# TestServoCircuit.net
KiCad netlist of a schematic drawn in Altium Designer
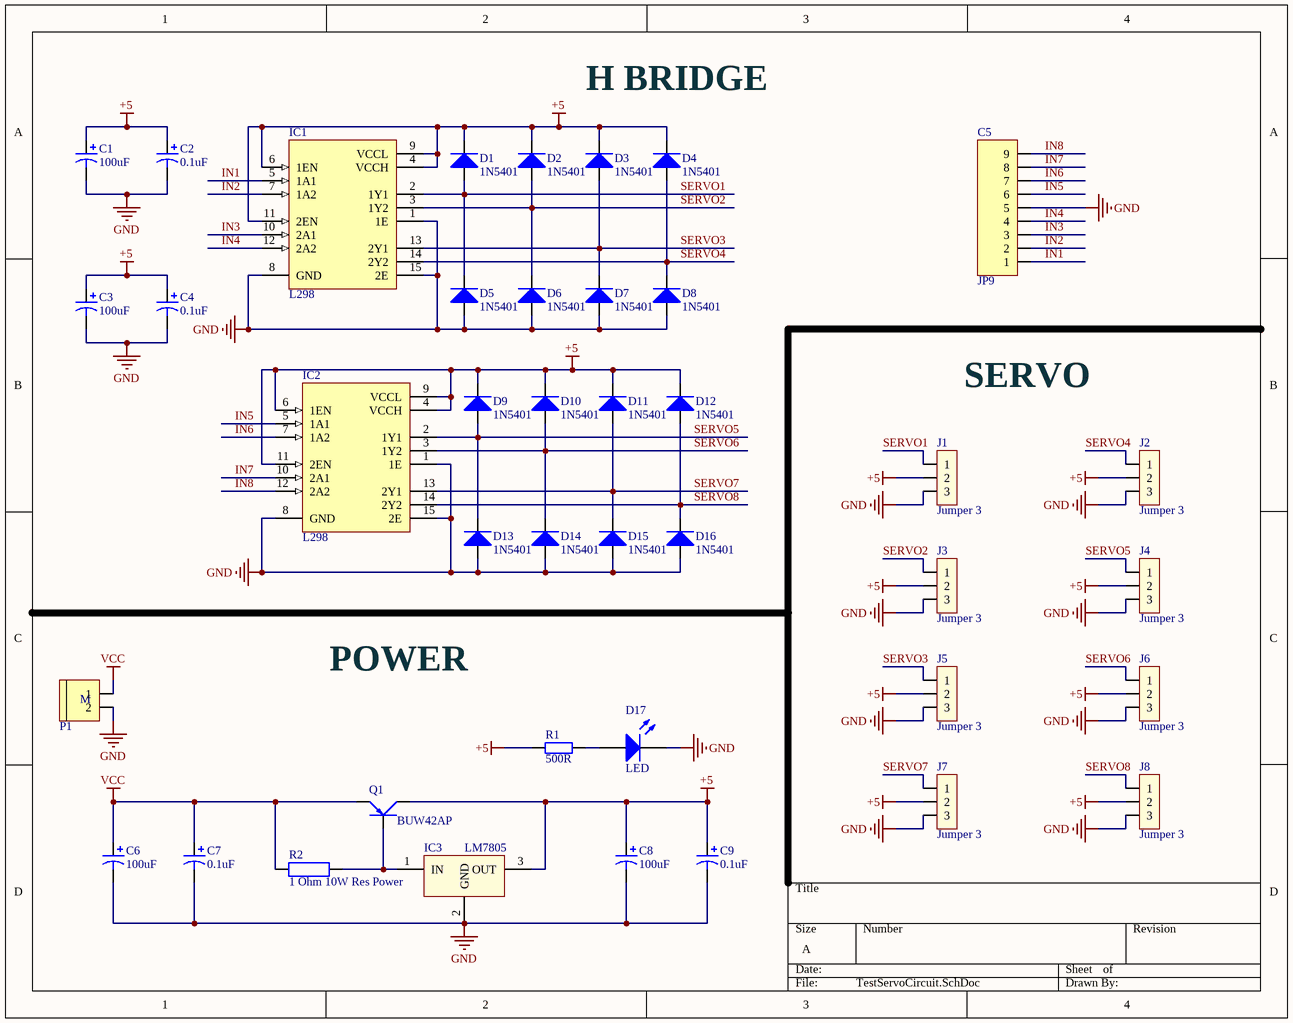
[diagram p0: TestServoCircuit.SchDoc]

(export (version "E")
  (design (tool "Eeschema 10.0.6"))
  (components
    (comp (ref "C1")
      (value "100uF")
      (footprint "MinhTien_PCBLib:CAPPR3-8x12")
      (description "Polarized Capacitor")
      (fields (field (name "Comment") "Cap Polar") (field (name "PUBLISHER") "Altium Limited"))
      (libsource (lib "MinhTien_SCHLib") (part "Cap Polar"))
    )
    (comp (ref "C2")
      (value "0.1uF")
      (footprint "MinhTien_PCBLib:CAPPR2-5x11")
      (description "Polarized Capacitor")
      (fields (field (name "Comment") "Cap Polar") (field (name "PUBLISHER") "Altium Limited"))
      (libsource (lib "MinhTien_SCHLib") (part "Cap Polar"))
    )
    (comp (ref "C3")
      (value "100uF")
      (footprint "MinhTien_PCBLib:CAPPR3-8x12")
      (description "Polarized Capacitor")
      (fields (field (name "Comment") "Cap Polar") (field (name "PUBLISHER") "Altium Limited"))
      (libsource (lib "MinhTien_SCHLib") (part "Cap Polar"))
    )
    (comp (ref "C4")
      (value "0.1uF")
      (footprint "MinhTien_PCBLib:CAPPR2-5x11")
      (description "Polarized Capacitor")
      (fields (field (name "Comment") "Cap Polar") (field (name "PUBLISHER") "Altium Limited"))
      (libsource (lib "MinhTien_SCHLib") (part "Cap Polar"))
    )
    (comp (ref "C5")
      (value "JP9")
      (footprint "JP9-D1T")
      (description "WR-PHD 2.54 mm Angled Socket Header")
      (fields
        (field (name "MANUFACTURER") "Würth Elektronik eiSos GmbH")
        (field (name "PARTNO") "613009143121")
        (field (name "CREATED BY") "Karrer Zheng")
      )
      (libsource (lib "LIBRARY") (part "JP9"))
    )
    (comp (ref "C6")
      (value "100uF")
      (footprint "MinhTien_PCBLib:CAPPR3-8x12")
      (description "Polarized Capacitor")
      (fields (field (name "Comment") "Cap Polar") (field (name "PUBLISHER") "Altium Limited"))
      (libsource (lib "MinhTien_SCHLib") (part "Cap Polar"))
    )
    (comp (ref "C7")
      (value "0.1uF")
      (footprint "MinhTien_PCBLib:CAPPR2-5x11")
      (description "Polarized Capacitor")
      (fields (field (name "Comment") "Cap Polar") (field (name "PUBLISHER") "Altium Limited"))
      (libsource (lib "MinhTien_SCHLib") (part "Cap Polar"))
    )
    (comp (ref "C8")
      (value "100uF")
      (footprint "MinhTien_PCBLib:CAPPR3-8x12")
      (description "Polarized Capacitor")
      (fields (field (name "Comment") "Cap Polar") (field (name "PUBLISHER") "Altium Limited"))
      (libsource (lib "MinhTien_SCHLib") (part "Cap Polar"))
    )
    (comp (ref "C9")
      (value "0.1uF")
      (footprint "MinhTien_PCBLib:CAPPR2-5x11")
      (description "Polarized Capacitor")
      (fields (field (name "Comment") "Cap Polar") (field (name "PUBLISHER") "Altium Limited"))
      (libsource (lib "MinhTien_SCHLib") (part "Cap Polar"))
    )
    (comp (ref "D1")
      (value "1N5401")
      (footprint "MinhTien_PcbLib:DIODE/POW/3A")
      (description "Default Diode")
      (fields (field (name "PUBLISHER") "Altium Limited"))
      (libsource (lib "MinhTien_SCHLib") (part "Diode"))
    )
    (comp (ref "D2")
      (value "1N5401")
      (footprint "MinhTien_PcbLib:DIODE/POW/3A")
      (description "Default Diode")
      (fields (field (name "PUBLISHER") "Altium Limited"))
      (libsource (lib "MinhTien_SCHLib") (part "Diode"))
    )
    (comp (ref "D3")
      (value "1N5401")
      (footprint "MinhTien_PcbLib:DIODE/POW/3A")
      (description "Default Diode")
      (fields (field (name "PUBLISHER") "Altium Limited"))
      (libsource (lib "MinhTien_SCHLib") (part "Diode"))
    )
    (comp (ref "D4")
      (value "1N5401")
      (footprint "MinhTien_PcbLib:DIODE/POW/3A")
      (description "Default Diode")
      (fields (field (name "PUBLISHER") "Altium Limited"))
      (libsource (lib "MinhTien_SCHLib") (part "Diode"))
    )
    (comp (ref "D5")
      (value "1N5401")
      (footprint "MinhTien_PcbLib:DIODE/POW/3A")
      (description "Default Diode")
      (fields (field (name "PUBLISHER") "Altium Limited"))
      (libsource (lib "MinhTien_SCHLib") (part "Diode"))
    )
    (comp (ref "D6")
      (value "1N5401")
      (footprint "MinhTien_PcbLib:DIODE/POW/3A")
      (description "Default Diode")
      (fields (field (name "PUBLISHER") "Altium Limited"))
      (libsource (lib "MinhTien_SCHLib") (part "Diode"))
    )
    (comp (ref "D7")
      (value "1N5401")
      (footprint "MinhTien_PcbLib:DIODE/POW/3A")
      (description "Default Diode")
      (fields (field (name "PUBLISHER") "Altium Limited"))
      (libsource (lib "MinhTien_SCHLib") (part "Diode"))
    )
    (comp (ref "D8")
      (value "1N5401")
      (footprint "MinhTien_PcbLib:DIODE/POW/3A")
      (description "Default Diode")
      (fields (field (name "PUBLISHER") "Altium Limited"))
      (libsource (lib "MinhTien_SCHLib") (part "Diode"))
    )
    (comp (ref "D9")
      (value "1N5401")
      (footprint "MinhTien_PcbLib:DIODE/POW/3A")
      (description "Default Diode")
      (fields (field (name "PUBLISHER") "Altium Limited"))
      (libsource (lib "MinhTien_SCHLib") (part "Diode"))
    )
    (comp (ref "D10")
      (value "1N5401")
      (footprint "MinhTien_PcbLib:DIODE/POW/3A")
      (description "Default Diode")
      (fields (field (name "PUBLISHER") "Altium Limited"))
      (libsource (lib "MinhTien_SCHLib") (part "Diode"))
    )
    (comp (ref "D11")
      (value "1N5401")
      (footprint "MinhTien_PcbLib:DIODE/POW/3A")
      (description "Default Diode")
      (fields (field (name "PUBLISHER") "Altium Limited"))
      (libsource (lib "MinhTien_SCHLib") (part "Diode"))
    )
    (comp (ref "D12")
      (value "1N5401")
      (footprint "MinhTien_PcbLib:DIODE/POW/3A")
      (description "Default Diode")
      (fields (field (name "PUBLISHER") "Altium Limited"))
      (libsource (lib "MinhTien_SCHLib") (part "Diode"))
    )
    (comp (ref "D13")
      (value "1N5401")
      (footprint "MinhTien_PcbLib:DIODE/POW/3A")
      (description "Default Diode")
      (fields (field (name "PUBLISHER") "Altium Limited"))
      (libsource (lib "MinhTien_SCHLib") (part "Diode"))
    )
    (comp (ref "D14")
      (value "1N5401")
      (footprint "MinhTien_PcbLib:DIODE/POW/3A")
      (description "Default Diode")
      (fields (field (name "PUBLISHER") "Altium Limited"))
      (libsource (lib "MinhTien_SCHLib") (part "Diode"))
    )
    (comp (ref "D15")
      (value "1N5401")
      (footprint "MinhTien_PcbLib:DIODE/POW/3A")
      (description "Default Diode")
      (fields (field (name "PUBLISHER") "Altium Limited"))
      (libsource (lib "MinhTien_SCHLib") (part "Diode"))
    )
    (comp (ref "D16")
      (value "1N5401")
      (footprint "MinhTien_PcbLib:DIODE/POW/3A")
      (description "Default Diode")
      (fields (field (name "PUBLISHER") "Altium Limited"))
      (libsource (lib "MinhTien_SCHLib") (part "Diode"))
    )
    (comp (ref "D17")
      (value "LED")
      (footprint "MinhTien_PcbLib:LED_5mm")
      (description "Typical INFRARED GaAs LED")
      (fields (field (name "PUBLISHER") "Altium Limited"))
      (libsource (lib "MinhTien_SCHLib") (part "LED"))
    )
    (comp (ref "IC1")
      (value "L298")
      (footprint "DIP15SL2")
      (description "Dual Full-H Driver")
      (fields (field (name "PUBLISHER") "Altium Limited"))
      (libsource (lib "LIBRARY") (part "L298"))
    )
    (comp (ref "IC2")
      (value "L298")
      (footprint "DIP15SL2")
      (description "Dual Full-H Driver")
      (fields (field (name "PUBLISHER") "Altium Limited"))
      (libsource (lib "LIBRARY") (part "L298"))
    )
    (comp (ref "IC3")
      (value "LM7805")
      (footprint "QTO-220")
      (description "On ap +, from + 5 to + 24VDC")
      (libsource (lib "My Library") (part "LM78xx"))
    )
    (comp (ref "J1") (value "Jumper 3") (footprint "JP3") (libsource (lib "Cty1") (part "JP3")))
    (comp (ref "J2") (value "Jumper 3") (footprint "JP3") (libsource (lib "Cty1") (part "JP3")))
    (comp (ref "J3") (value "Jumper 3") (footprint "JP3") (libsource (lib "Cty1") (part "JP3")))
    (comp (ref "J4") (value "Jumper 3") (footprint "JP3") (libsource (lib "Cty1") (part "JP3")))
    (comp (ref "J5") (value "Jumper 3") (footprint "JP3") (libsource (lib "Cty1") (part "JP3")))
    (comp (ref "J6") (value "Jumper 3") (footprint "JP3") (libsource (lib "Cty1") (part "JP3")))
    (comp (ref "J7") (value "Jumper 3") (footprint "JP3") (libsource (lib "Cty1") (part "JP3")))
    (comp (ref "J8") (value "Jumper 3") (footprint "JP3") (libsource (lib "Cty1") (part "JP3")))
    (comp (ref "P1")
      (value "KF301 Domino 2")
      (footprint "vanthinh:Header 2 - M")
      (description "TERM BLOCK PLUG 2POS 5MM")
      (fields
        (field (name "MANUFACTURER") "On-Shore Technology")
        (field (name "MANUFACTURER PART NUMBER") "KF301")
      )
      (libsource (lib "vanthinh") (part "HEADER 2 - M"))
    )
    (comp (ref "Q1")
      (value "BUW42AP")
      (footprint "vanthinh:TO-3P")
      (libsource (lib "vanthinh") (part "PNP_BCE"))
    )
    (comp (ref "R1")
      (value "500R")
      (footprint "DIEN TRO 1/4 W")
      (description "Resistor")
      (fields (field (name "Comment") "R0.4W") (field (name "PUBLISHER") "Altium Limited"))
      (libsource (lib "My Library") (part "Res 1/4 W"))
    )
    (comp (ref "R2")
      (value "1 Ohm 10W Res Power")
      (footprint "DIEN TRO 10W")
      (description "10W Res Power")
      (fields (field (name "CREATOR") "Nguyen Ba Bien"))
      (libsource (lib "Cty1") (part "Res 10 W"))
    )
  )
  (nets
    (net (code "1") (name "+5") (class "Default")
      (node (ref "C1") (pin "1") (pinfunction "1_1") (pintype "passive"))
      (node (ref "C2") (pin "1") (pinfunction "1_1") (pintype "passive"))
      (node (ref "C3") (pin "1") (pinfunction "1_1") (pintype "passive"))
      (node (ref "C4") (pin "1") (pinfunction "1_1") (pintype "passive"))
      (node (ref "C8") (pin "1") (pinfunction "1_1") (pintype "passive"))
      (node (ref "C9") (pin "1") (pinfunction "1_1") (pintype "passive"))
      (node (ref "D1") (pin "2") (pinfunction "K_2") (pintype "passive"))
      (node (ref "D10") (pin "2") (pinfunction "K_2") (pintype "passive"))
      (node (ref "D11") (pin "2") (pinfunction "K_2") (pintype "passive"))
      (node (ref "D12") (pin "2") (pinfunction "K_2") (pintype "passive"))
      (node (ref "D2") (pin "2") (pinfunction "K_2") (pintype "passive"))
      (node (ref "D3") (pin "2") (pinfunction "K_2") (pintype "passive"))
      (node (ref "D4") (pin "2") (pinfunction "K_2") (pintype "passive"))
      (node (ref "D9") (pin "2") (pinfunction "K_2") (pintype "passive"))
      (node (ref "IC1") (pin "11") (pinfunction "2EN_11") (pintype "input"))
      (node (ref "IC1") (pin "4") (pinfunction "VCCH_4") (pintype "power_in"))
      (node (ref "IC1") (pin "6") (pinfunction "1EN_6") (pintype "input"))
      (node (ref "IC1") (pin "9") (pinfunction "VCCL_9") (pintype "power_in"))
      (node (ref "IC2") (pin "11") (pinfunction "2EN_11") (pintype "input"))
      (node (ref "IC2") (pin "4") (pinfunction "VCCH_4") (pintype "power_in"))
      (node (ref "IC2") (pin "6") (pinfunction "1EN_6") (pintype "input"))
      (node (ref "IC2") (pin "9") (pinfunction "VCCL_9") (pintype "power_in"))
      (node (ref "IC3") (pin "3") (pinfunction "OUT_3") (pintype "passive"))
      (node (ref "J1") (pin "2") (pinfunction "2_2") (pintype "passive"))
      (node (ref "J2") (pin "2") (pinfunction "2_2") (pintype "passive"))
      (node (ref "J3") (pin "2") (pinfunction "2_2") (pintype "passive"))
      (node (ref "J4") (pin "2") (pinfunction "2_2") (pintype "passive"))
      (node (ref "J5") (pin "2") (pinfunction "2_2") (pintype "passive"))
      (node (ref "J6") (pin "2") (pinfunction "2_2") (pintype "passive"))
      (node (ref "J7") (pin "2") (pinfunction "2_2") (pintype "passive"))
      (node (ref "J8") (pin "2") (pinfunction "2_2") (pintype "passive"))
      (node (ref "Q1") (pin "2") (pinfunction "C_2") (pintype "passive"))
      (node (ref "R1") (pin "1") (pinfunction "1_1") (pintype "passive"))
    )
    (net (code "2") (name "/IN1") (class "Default")
      (node (ref "C5") (pin "1") (pinfunction "1_1") (pintype "passive"))
      (node (ref "IC1") (pin "5") (pinfunction "1A1_5") (pintype "input"))
    )
    (net (code "3") (name "/IN2") (class "Default")
      (node (ref "C5") (pin "2") (pinfunction "2_2") (pintype "passive"))
      (node (ref "IC1") (pin "7") (pinfunction "1A2_7") (pintype "input"))
    )
    (net (code "4") (name "/IN3") (class "Default")
      (node (ref "C5") (pin "3") (pinfunction "3_3") (pintype "passive"))
      (node (ref "IC1") (pin "10") (pinfunction "2A1_10") (pintype "input"))
    )
    (net (code "5") (name "/IN4") (class "Default")
      (node (ref "C5") (pin "4") (pinfunction "4_4") (pintype "passive"))
      (node (ref "IC1") (pin "12") (pinfunction "2A2_12") (pintype "input"))
    )
    (net (code "6") (name "/IN5") (class "Default")
      (node (ref "C5") (pin "6") (pinfunction "6_6") (pintype "passive"))
      (node (ref "IC2") (pin "5") (pinfunction "1A1_5") (pintype "input"))
    )
    (net (code "7") (name "/IN6") (class "Default")
      (node (ref "C5") (pin "7") (pinfunction "7_7") (pintype "passive"))
      (node (ref "IC2") (pin "7") (pinfunction "1A2_7") (pintype "input"))
    )
    (net (code "8") (name "/IN7") (class "Default")
      (node (ref "C5") (pin "8") (pinfunction "8_8") (pintype "passive"))
      (node (ref "IC2") (pin "10") (pinfunction "2A1_10") (pintype "input"))
    )
    (net (code "9") (name "/IN8") (class "Default")
      (node (ref "C5") (pin "9") (pinfunction "9_9") (pintype "passive"))
      (node (ref "IC2") (pin "12") (pinfunction "2A2_12") (pintype "input"))
    )
    (net (code "10") (name "/SERVO1") (class "Default")
      (node (ref "D1") (pin "1") (pinfunction "A_1") (pintype "passive"))
      (node (ref "D5") (pin "2") (pinfunction "K_2") (pintype "passive"))
      (node (ref "IC1") (pin "2") (pinfunction "1Y1_2") (pintype "tri_state"))
      (node (ref "J1") (pin "1") (pinfunction "1_1") (pintype "passive"))
    )
    (net (code "11") (name "/SERVO2") (class "Default")
      (node (ref "D2") (pin "1") (pinfunction "A_1") (pintype "passive"))
      (node (ref "D6") (pin "2") (pinfunction "K_2") (pintype "passive"))
      (node (ref "IC1") (pin "3") (pinfunction "1Y2_3") (pintype "tri_state"))
      (node (ref "J3") (pin "1") (pinfunction "1_1") (pintype "passive"))
    )
    (net (code "12") (name "/SERVO3") (class "Default")
      (node (ref "D3") (pin "1") (pinfunction "A_1") (pintype "passive"))
      (node (ref "D7") (pin "2") (pinfunction "K_2") (pintype "passive"))
      (node (ref "IC1") (pin "13") (pinfunction "2Y1_13") (pintype "tri_state"))
      (node (ref "J5") (pin "1") (pinfunction "1_1") (pintype "passive"))
    )
    (net (code "13") (name "/SERVO4") (class "Default")
      (node (ref "D4") (pin "1") (pinfunction "A_1") (pintype "passive"))
      (node (ref "D8") (pin "2") (pinfunction "K_2") (pintype "passive"))
      (node (ref "IC1") (pin "14") (pinfunction "2Y2_14") (pintype "tri_state"))
      (node (ref "J2") (pin "1") (pinfunction "1_1") (pintype "passive"))
    )
    (net (code "14") (name "/SERVO5") (class "Default")
      (node (ref "D13") (pin "2") (pinfunction "K_2") (pintype "passive"))
      (node (ref "D9") (pin "1") (pinfunction "A_1") (pintype "passive"))
      (node (ref "IC2") (pin "2") (pinfunction "1Y1_2") (pintype "tri_state"))
      (node (ref "J4") (pin "1") (pinfunction "1_1") (pintype "passive"))
    )
    (net (code "15") (name "/SERVO6") (class "Default")
      (node (ref "D10") (pin "1") (pinfunction "A_1") (pintype "passive"))
      (node (ref "D14") (pin "2") (pinfunction "K_2") (pintype "passive"))
      (node (ref "IC2") (pin "3") (pinfunction "1Y2_3") (pintype "tri_state"))
      (node (ref "J6") (pin "1") (pinfunction "1_1") (pintype "passive"))
    )
    (net (code "16") (name "/SERVO7") (class "Default")
      (node (ref "D11") (pin "1") (pinfunction "A_1") (pintype "passive"))
      (node (ref "D15") (pin "2") (pinfunction "K_2") (pintype "passive"))
      (node (ref "IC2") (pin "13") (pinfunction "2Y1_13") (pintype "tri_state"))
      (node (ref "J7") (pin "1") (pinfunction "1_1") (pintype "passive"))
    )
    (net (code "17") (name "/SERVO8") (class "Default")
      (node (ref "D12") (pin "1") (pinfunction "A_1") (pintype "passive"))
      (node (ref "D16") (pin "2") (pinfunction "K_2") (pintype "passive"))
      (node (ref "IC2") (pin "14") (pinfunction "2Y2_14") (pintype "tri_state"))
      (node (ref "J8") (pin "1") (pinfunction "1_1") (pintype "passive"))
    )
    (net (code "18") (name "GND") (class "Default")
      (node (ref "C1") (pin "2") (pinfunction "2_2") (pintype "passive"))
      (node (ref "C2") (pin "2") (pinfunction "2_2") (pintype "passive"))
      (node (ref "C3") (pin "2") (pinfunction "2_2") (pintype "passive"))
      (node (ref "C4") (pin "2") (pinfunction "2_2") (pintype "passive"))
      (node (ref "C5") (pin "5") (pinfunction "5_5") (pintype "passive"))
      (node (ref "C6") (pin "2") (pinfunction "2_2") (pintype "passive"))
      (node (ref "C7") (pin "2") (pinfunction "2_2") (pintype "passive"))
      (node (ref "C8") (pin "2") (pinfunction "2_2") (pintype "passive"))
      (node (ref "C9") (pin "2") (pinfunction "2_2") (pintype "passive"))
      (node (ref "D13") (pin "1") (pinfunction "A_1") (pintype "passive"))
      (node (ref "D14") (pin "1") (pinfunction "A_1") (pintype "passive"))
      (node (ref "D15") (pin "1") (pinfunction "A_1") (pintype "passive"))
      (node (ref "D16") (pin "1") (pinfunction "A_1") (pintype "passive"))
      (node (ref "D17") (pin "2") (pinfunction "K_2") (pintype "passive"))
      (node (ref "D5") (pin "1") (pinfunction "A_1") (pintype "passive"))
      (node (ref "D6") (pin "1") (pinfunction "A_1") (pintype "passive"))
      (node (ref "D7") (pin "1") (pinfunction "A_1") (pintype "passive"))
      (node (ref "D8") (pin "1") (pinfunction "A_1") (pintype "passive"))
      (node (ref "IC1") (pin "1") (pinfunction "1E_1") (pintype "passive"))
      (node (ref "IC1") (pin "15") (pinfunction "2E_15") (pintype "passive"))
      (node (ref "IC1") (pin "8") (pinfunction "GND_8") (pintype "power_in"))
      (node (ref "IC2") (pin "1") (pinfunction "1E_1") (pintype "passive"))
      (node (ref "IC2") (pin "15") (pinfunction "2E_15") (pintype "passive"))
      (node (ref "IC2") (pin "8") (pinfunction "GND_8") (pintype "power_in"))
      (node (ref "IC3") (pin "2") (pinfunction "GND_2") (pintype "passive"))
      (node (ref "J1") (pin "3") (pinfunction "3_3") (pintype "passive"))
      (node (ref "J2") (pin "3") (pinfunction "3_3") (pintype "passive"))
      (node (ref "J3") (pin "3") (pinfunction "3_3") (pintype "passive"))
      (node (ref "J4") (pin "3") (pinfunction "3_3") (pintype "passive"))
      (node (ref "J5") (pin "3") (pinfunction "3_3") (pintype "passive"))
      (node (ref "J6") (pin "3") (pinfunction "3_3") (pintype "passive"))
      (node (ref "J7") (pin "3") (pinfunction "3_3") (pintype "passive"))
      (node (ref "J8") (pin "3") (pinfunction "3_3") (pintype "passive"))
      (node (ref "P1") (pin "2") (pinfunction "2_2") (pintype "passive"))
    )
    (net (code "19") (name "Net-(D17-A)") (class "Default")
      (node (ref "D17") (pin "1") (pinfunction "A_1") (pintype "passive"))
      (node (ref "R1") (pin "2") (pinfunction "2_2") (pintype "passive"))
    )
    (net (code "20") (name "Net-(IC3-IN)") (class "Default")
      (node (ref "IC3") (pin "1") (pinfunction "IN_1") (pintype "passive"))
      (node (ref "Q1") (pin "1") (pinfunction "B_1") (pintype "passive"))
      (node (ref "R2") (pin "2") (pinfunction "2_2") (pintype "passive"))
    )
    (net (code "21") (name "VCC") (class "Default")
      (node (ref "C6") (pin "1") (pinfunction "1_1") (pintype "passive"))
      (node (ref "C7") (pin "1") (pinfunction "1_1") (pintype "passive"))
      (node (ref "P1") (pin "1") (pinfunction "1_1") (pintype "passive"))
      (node (ref "Q1") (pin "3") (pinfunction "E_3") (pintype "passive"))
      (node (ref "R2") (pin "1") (pinfunction "1_1") (pintype "passive"))
    )
  )
)
